# SevenSegmentBreakout.net
KiCad netlist of a schematic drawn in EAGLE
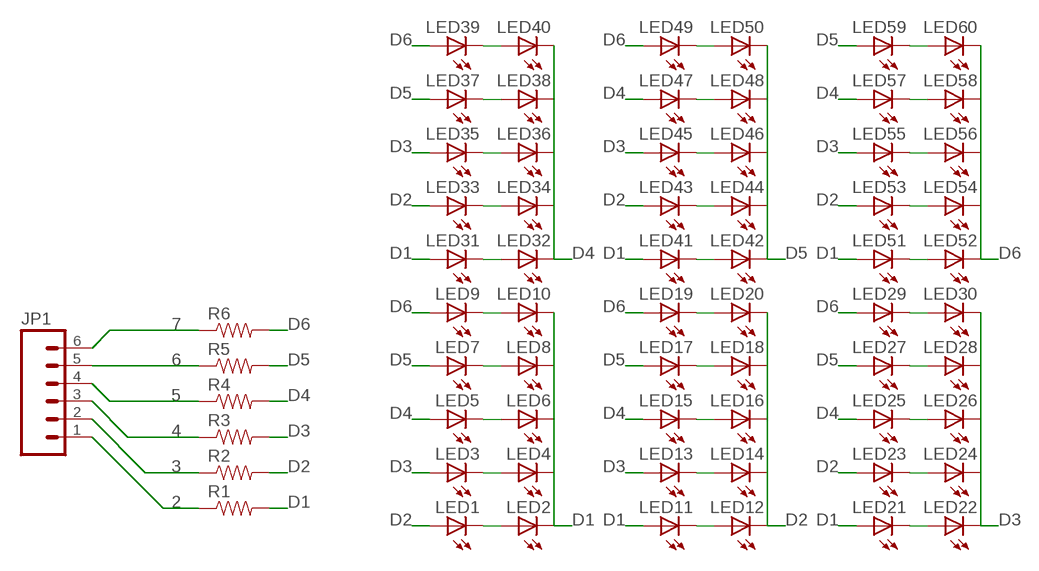
[diagram p0: schematic, sheet 1]

(export (version "E")
  (design (tool "Eeschema 10.0.6"))
  (components
    (comp (ref "JP1")
      (value "M06SIP")
      (footprint "eagle-import:1X06")
      (libsource (lib "eagle-import") (part "M06SIP"))
    )
    (comp (ref "LED1")
      (value "LEDRECT")
      (footprint "eagle-import:RECTANGLE_LED")
      (libsource (lib "eagle-import") (part "LEDRECT"))
    )
    (comp (ref "LED2")
      (value "LEDRECT")
      (footprint "eagle-import:RECTANGLE_LED")
      (libsource (lib "eagle-import") (part "LEDRECT"))
    )
    (comp (ref "LED3")
      (value "LEDRECT")
      (footprint "eagle-import:RECTANGLE_LED")
      (libsource (lib "eagle-import") (part "LEDRECT"))
    )
    (comp (ref "LED4")
      (value "LEDRECT")
      (footprint "eagle-import:RECTANGLE_LED")
      (libsource (lib "eagle-import") (part "LEDRECT"))
    )
    (comp (ref "LED5")
      (value "LEDRECT")
      (footprint "eagle-import:RECTANGLE_LED")
      (libsource (lib "eagle-import") (part "LEDRECT"))
    )
    (comp (ref "LED6")
      (value "LEDRECT")
      (footprint "eagle-import:RECTANGLE_LED")
      (libsource (lib "eagle-import") (part "LEDRECT"))
    )
    (comp (ref "LED7")
      (value "LEDRECT")
      (footprint "eagle-import:RECTANGLE_LED")
      (libsource (lib "eagle-import") (part "LEDRECT"))
    )
    (comp (ref "LED8")
      (value "LEDRECT")
      (footprint "eagle-import:RECTANGLE_LED")
      (libsource (lib "eagle-import") (part "LEDRECT"))
    )
    (comp (ref "LED9")
      (value "LEDRECT")
      (footprint "eagle-import:RECTANGLE_LED")
      (libsource (lib "eagle-import") (part "LEDRECT"))
    )
    (comp (ref "LED10")
      (value "LEDRECT")
      (footprint "eagle-import:RECTANGLE_LED")
      (libsource (lib "eagle-import") (part "LEDRECT"))
    )
    (comp (ref "LED11")
      (value "LEDRECT")
      (footprint "eagle-import:RECTANGLE_LED")
      (libsource (lib "eagle-import") (part "LEDRECT"))
    )
    (comp (ref "LED12")
      (value "LEDRECT")
      (footprint "eagle-import:RECTANGLE_LED")
      (libsource (lib "eagle-import") (part "LEDRECT"))
    )
    (comp (ref "LED13")
      (value "LEDRECT")
      (footprint "eagle-import:RECTANGLE_LED")
      (libsource (lib "eagle-import") (part "LEDRECT"))
    )
    (comp (ref "LED14")
      (value "LEDRECT")
      (footprint "eagle-import:RECTANGLE_LED")
      (libsource (lib "eagle-import") (part "LEDRECT"))
    )
    (comp (ref "LED15")
      (value "LEDRECT")
      (footprint "eagle-import:RECTANGLE_LED")
      (libsource (lib "eagle-import") (part "LEDRECT"))
    )
    (comp (ref "LED16")
      (value "LEDRECT")
      (footprint "eagle-import:RECTANGLE_LED")
      (libsource (lib "eagle-import") (part "LEDRECT"))
    )
    (comp (ref "LED17")
      (value "LEDRECT")
      (footprint "eagle-import:RECTANGLE_LED")
      (libsource (lib "eagle-import") (part "LEDRECT"))
    )
    (comp (ref "LED18")
      (value "LEDRECT")
      (footprint "eagle-import:RECTANGLE_LED")
      (libsource (lib "eagle-import") (part "LEDRECT"))
    )
    (comp (ref "LED19")
      (value "LEDRECT")
      (footprint "eagle-import:RECTANGLE_LED")
      (libsource (lib "eagle-import") (part "LEDRECT"))
    )
    (comp (ref "LED20")
      (value "LEDRECT")
      (footprint "eagle-import:RECTANGLE_LED")
      (libsource (lib "eagle-import") (part "LEDRECT"))
    )
    (comp (ref "LED21")
      (value "LEDRECT")
      (footprint "eagle-import:RECTANGLE_LED")
      (libsource (lib "eagle-import") (part "LEDRECT"))
    )
    (comp (ref "LED22")
      (value "LEDRECT")
      (footprint "eagle-import:RECTANGLE_LED")
      (libsource (lib "eagle-import") (part "LEDRECT"))
    )
    (comp (ref "LED23")
      (value "LEDRECT")
      (footprint "eagle-import:RECTANGLE_LED")
      (libsource (lib "eagle-import") (part "LEDRECT"))
    )
    (comp (ref "LED24")
      (value "LEDRECT")
      (footprint "eagle-import:RECTANGLE_LED")
      (libsource (lib "eagle-import") (part "LEDRECT"))
    )
    (comp (ref "LED25")
      (value "LEDRECT")
      (footprint "eagle-import:RECTANGLE_LED")
      (libsource (lib "eagle-import") (part "LEDRECT"))
    )
    (comp (ref "LED26")
      (value "LEDRECT")
      (footprint "eagle-import:RECTANGLE_LED")
      (libsource (lib "eagle-import") (part "LEDRECT"))
    )
    (comp (ref "LED27")
      (value "LEDRECT")
      (footprint "eagle-import:RECTANGLE_LED")
      (libsource (lib "eagle-import") (part "LEDRECT"))
    )
    (comp (ref "LED28")
      (value "LEDRECT")
      (footprint "eagle-import:RECTANGLE_LED")
      (libsource (lib "eagle-import") (part "LEDRECT"))
    )
    (comp (ref "LED29")
      (value "LEDRECT")
      (footprint "eagle-import:RECTANGLE_LED")
      (libsource (lib "eagle-import") (part "LEDRECT"))
    )
    (comp (ref "LED30")
      (value "LEDRECT")
      (footprint "eagle-import:RECTANGLE_LED")
      (libsource (lib "eagle-import") (part "LEDRECT"))
    )
    (comp (ref "LED31")
      (value "LEDRECT")
      (footprint "eagle-import:RECTANGLE_LED")
      (libsource (lib "eagle-import") (part "LEDRECT"))
    )
    (comp (ref "LED32")
      (value "LEDRECT")
      (footprint "eagle-import:RECTANGLE_LED")
      (libsource (lib "eagle-import") (part "LEDRECT"))
    )
    (comp (ref "LED33")
      (value "LEDRECT")
      (footprint "eagle-import:RECTANGLE_LED")
      (libsource (lib "eagle-import") (part "LEDRECT"))
    )
    (comp (ref "LED34")
      (value "LEDRECT")
      (footprint "eagle-import:RECTANGLE_LED")
      (libsource (lib "eagle-import") (part "LEDRECT"))
    )
    (comp (ref "LED35")
      (value "LEDRECT")
      (footprint "eagle-import:RECTANGLE_LED")
      (libsource (lib "eagle-import") (part "LEDRECT"))
    )
    (comp (ref "LED36")
      (value "LEDRECT")
      (footprint "eagle-import:RECTANGLE_LED")
      (libsource (lib "eagle-import") (part "LEDRECT"))
    )
    (comp (ref "LED37")
      (value "LEDRECT")
      (footprint "eagle-import:RECTANGLE_LED")
      (libsource (lib "eagle-import") (part "LEDRECT"))
    )
    (comp (ref "LED38")
      (value "LEDRECT")
      (footprint "eagle-import:RECTANGLE_LED")
      (libsource (lib "eagle-import") (part "LEDRECT"))
    )
    (comp (ref "LED39")
      (value "LEDRECT")
      (footprint "eagle-import:RECTANGLE_LED")
      (libsource (lib "eagle-import") (part "LEDRECT"))
    )
    (comp (ref "LED40")
      (value "LEDRECT")
      (footprint "eagle-import:RECTANGLE_LED")
      (libsource (lib "eagle-import") (part "LEDRECT"))
    )
    (comp (ref "LED41")
      (value "LEDRECT")
      (footprint "eagle-import:RECTANGLE_LED")
      (libsource (lib "eagle-import") (part "LEDRECT"))
    )
    (comp (ref "LED42")
      (value "LEDRECT")
      (footprint "eagle-import:RECTANGLE_LED")
      (libsource (lib "eagle-import") (part "LEDRECT"))
    )
    (comp (ref "LED43")
      (value "LEDRECT")
      (footprint "eagle-import:RECTANGLE_LED")
      (libsource (lib "eagle-import") (part "LEDRECT"))
    )
    (comp (ref "LED44")
      (value "LEDRECT")
      (footprint "eagle-import:RECTANGLE_LED")
      (libsource (lib "eagle-import") (part "LEDRECT"))
    )
    (comp (ref "LED45")
      (value "LEDRECT")
      (footprint "eagle-import:RECTANGLE_LED")
      (libsource (lib "eagle-import") (part "LEDRECT"))
    )
    (comp (ref "LED46")
      (value "LEDRECT")
      (footprint "eagle-import:RECTANGLE_LED")
      (libsource (lib "eagle-import") (part "LEDRECT"))
    )
    (comp (ref "LED47")
      (value "LEDRECT")
      (footprint "eagle-import:RECTANGLE_LED")
      (libsource (lib "eagle-import") (part "LEDRECT"))
    )
    (comp (ref "LED48")
      (value "LEDRECT")
      (footprint "eagle-import:RECTANGLE_LED")
      (libsource (lib "eagle-import") (part "LEDRECT"))
    )
    (comp (ref "LED49")
      (value "LEDRECT")
      (footprint "eagle-import:RECTANGLE_LED")
      (libsource (lib "eagle-import") (part "LEDRECT"))
    )
    (comp (ref "LED50")
      (value "LEDRECT")
      (footprint "eagle-import:RECTANGLE_LED")
      (libsource (lib "eagle-import") (part "LEDRECT"))
    )
    (comp (ref "LED51")
      (value "LEDRECT")
      (footprint "eagle-import:RECTANGLE_LED")
      (libsource (lib "eagle-import") (part "LEDRECT"))
    )
    (comp (ref "LED52")
      (value "LEDRECT")
      (footprint "eagle-import:RECTANGLE_LED")
      (libsource (lib "eagle-import") (part "LEDRECT"))
    )
    (comp (ref "LED53")
      (value "LEDRECT")
      (footprint "eagle-import:RECTANGLE_LED")
      (libsource (lib "eagle-import") (part "LEDRECT"))
    )
    (comp (ref "LED54")
      (value "LEDRECT")
      (footprint "eagle-import:RECTANGLE_LED")
      (libsource (lib "eagle-import") (part "LEDRECT"))
    )
    (comp (ref "LED55")
      (value "LEDRECT")
      (footprint "eagle-import:RECTANGLE_LED")
      (libsource (lib "eagle-import") (part "LEDRECT"))
    )
    (comp (ref "LED56")
      (value "LEDRECT")
      (footprint "eagle-import:RECTANGLE_LED")
      (libsource (lib "eagle-import") (part "LEDRECT"))
    )
    (comp (ref "LED57")
      (value "LEDOVAL")
      (footprint "eagle-import:LED-OVAL")
      (libsource (lib "eagle-import") (part "LEDOVAL"))
    )
    (comp (ref "LED58")
      (value "LEDOVAL")
      (footprint "eagle-import:LED-OVAL")
      (libsource (lib "eagle-import") (part "LEDOVAL"))
    )
    (comp (ref "LED59")
      (value "LEDOVAL")
      (footprint "eagle-import:LED-OVAL")
      (libsource (lib "eagle-import") (part "LEDOVAL"))
    )
    (comp (ref "LED60")
      (value "LEDOVAL")
      (footprint "eagle-import:LED-OVAL")
      (libsource (lib "eagle-import") (part "LEDOVAL"))
    )
    (comp (ref "R1")
      (value "RESISTORAXIAL-0.3")
      (footprint "eagle-import:AXIAL-0.3")
      (libsource (lib "eagle-import") (part "RESISTORAXIAL-0.3"))
    )
    (comp (ref "R2")
      (value "RESISTORAXIAL-0.3")
      (footprint "eagle-import:AXIAL-0.3")
      (libsource (lib "eagle-import") (part "RESISTORAXIAL-0.3"))
    )
    (comp (ref "R3")
      (value "RESISTORAXIAL-0.3")
      (footprint "eagle-import:AXIAL-0.3")
      (libsource (lib "eagle-import") (part "RESISTORAXIAL-0.3"))
    )
    (comp (ref "R4")
      (value "RESISTORAXIAL-0.3")
      (footprint "eagle-import:AXIAL-0.3")
      (libsource (lib "eagle-import") (part "RESISTORAXIAL-0.3"))
    )
    (comp (ref "R5")
      (value "RESISTORAXIAL-0.3")
      (footprint "eagle-import:AXIAL-0.3")
      (libsource (lib "eagle-import") (part "RESISTORAXIAL-0.3"))
    )
    (comp (ref "R6")
      (value "RESISTORAXIAL-0.3")
      (footprint "eagle-import:AXIAL-0.3")
      (libsource (lib "eagle-import") (part "RESISTORAXIAL-0.3"))
    )
  )
  (nets
    (net (code "1") (name "/2") (class "Default")
      (node (ref "JP1") (pin "1") (pinfunction "1_1") (pintype "passive"))
      (node (ref "R1") (pin "P$1") (pinfunction "1_P$1") (pintype "passive"))
    )
    (net (code "2") (name "/3") (class "Default")
      (node (ref "JP1") (pin "2") (pinfunction "2_2") (pintype "passive"))
      (node (ref "R2") (pin "P$1") (pinfunction "1_P$1") (pintype "passive"))
    )
    (net (code "3") (name "/4") (class "Default")
      (node (ref "JP1") (pin "3") (pinfunction "3_3") (pintype "passive"))
      (node (ref "R3") (pin "P$1") (pinfunction "1_P$1") (pintype "passive"))
    )
    (net (code "4") (name "/5") (class "Default")
      (node (ref "JP1") (pin "4") (pinfunction "4_4") (pintype "passive"))
      (node (ref "R4") (pin "P$1") (pinfunction "1_P$1") (pintype "passive"))
    )
    (net (code "5") (name "/6") (class "Default")
      (node (ref "JP1") (pin "5") (pinfunction "5_5") (pintype "passive"))
      (node (ref "R5") (pin "P$1") (pinfunction "1_P$1") (pintype "passive"))
    )
    (net (code "6") (name "/7") (class "Default")
      (node (ref "JP1") (pin "6") (pinfunction "6_6") (pintype "passive"))
      (node (ref "R6") (pin "P$1") (pinfunction "1_P$1") (pintype "passive"))
    )
    (net (code "7") (name "/D1") (class "Default")
      (node (ref "LED10") (pin "C") (pinfunction "C_C") (pintype "passive"))
      (node (ref "LED11") (pin "A") (pinfunction "A_A") (pintype "passive"))
      (node (ref "LED2") (pin "C") (pinfunction "C_C") (pintype "passive"))
      (node (ref "LED21") (pin "A") (pinfunction "A_A") (pintype "passive"))
      (node (ref "LED31") (pin "A") (pinfunction "A_A") (pintype "passive"))
      (node (ref "LED4") (pin "C") (pinfunction "C_C") (pintype "passive"))
      (node (ref "LED41") (pin "A") (pinfunction "A_A") (pintype "passive"))
      (node (ref "LED51") (pin "A") (pinfunction "A_A") (pintype "passive"))
      (node (ref "LED6") (pin "C") (pinfunction "C_C") (pintype "passive"))
      (node (ref "LED8") (pin "C") (pinfunction "C_C") (pintype "passive"))
      (node (ref "R1") (pin "P$2") (pinfunction "2_P$2") (pintype "passive"))
    )
    (net (code "8") (name "/D2") (class "Default")
      (node (ref "LED1") (pin "A") (pinfunction "A_A") (pintype "passive"))
      (node (ref "LED12") (pin "C") (pinfunction "C_C") (pintype "passive"))
      (node (ref "LED14") (pin "C") (pinfunction "C_C") (pintype "passive"))
      (node (ref "LED16") (pin "C") (pinfunction "C_C") (pintype "passive"))
      (node (ref "LED18") (pin "C") (pinfunction "C_C") (pintype "passive"))
      (node (ref "LED20") (pin "C") (pinfunction "C_C") (pintype "passive"))
      (node (ref "LED23") (pin "A") (pinfunction "A_A") (pintype "passive"))
      (node (ref "LED33") (pin "A") (pinfunction "A_A") (pintype "passive"))
      (node (ref "LED43") (pin "A") (pinfunction "A_A") (pintype "passive"))
      (node (ref "LED53") (pin "A") (pinfunction "A_A") (pintype "passive"))
      (node (ref "R2") (pin "P$2") (pinfunction "2_P$2") (pintype "passive"))
    )
    (net (code "9") (name "/D3") (class "Default")
      (node (ref "LED13") (pin "A") (pinfunction "A_A") (pintype "passive"))
      (node (ref "LED22") (pin "C") (pinfunction "C_C") (pintype "passive"))
      (node (ref "LED24") (pin "C") (pinfunction "C_C") (pintype "passive"))
      (node (ref "LED26") (pin "C") (pinfunction "C_C") (pintype "passive"))
      (node (ref "LED28") (pin "C") (pinfunction "C_C") (pintype "passive"))
      (node (ref "LED3") (pin "A") (pinfunction "A_A") (pintype "passive"))
      (node (ref "LED30") (pin "C") (pinfunction "C_C") (pintype "passive"))
      (node (ref "LED35") (pin "A") (pinfunction "A_A") (pintype "passive"))
      (node (ref "LED45") (pin "A") (pinfunction "A_A") (pintype "passive"))
      (node (ref "LED55") (pin "A") (pinfunction "A_A") (pintype "passive"))
      (node (ref "R3") (pin "P$2") (pinfunction "2_P$2") (pintype "passive"))
    )
    (net (code "10") (name "/D4") (class "Default")
      (node (ref "LED15") (pin "A") (pinfunction "A_A") (pintype "passive"))
      (node (ref "LED25") (pin "A") (pinfunction "A_A") (pintype "passive"))
      (node (ref "LED32") (pin "C") (pinfunction "C_C") (pintype "passive"))
      (node (ref "LED34") (pin "C") (pinfunction "C_C") (pintype "passive"))
      (node (ref "LED36") (pin "C") (pinfunction "C_C") (pintype "passive"))
      (node (ref "LED38") (pin "C") (pinfunction "C_C") (pintype "passive"))
      (node (ref "LED40") (pin "C") (pinfunction "C_C") (pintype "passive"))
      (node (ref "LED47") (pin "A") (pinfunction "A_A") (pintype "passive"))
      (node (ref "LED5") (pin "A") (pinfunction "A_A") (pintype "passive"))
      (node (ref "LED57") (pin "ANODE") (pinfunction "A_ANODE") (pintype "passive"))
      (node (ref "R4") (pin "P$2") (pinfunction "2_P$2") (pintype "passive"))
    )
    (net (code "11") (name "/D5") (class "Default")
      (node (ref "LED17") (pin "A") (pinfunction "A_A") (pintype "passive"))
      (node (ref "LED27") (pin "A") (pinfunction "A_A") (pintype "passive"))
      (node (ref "LED37") (pin "A") (pinfunction "A_A") (pintype "passive"))
      (node (ref "LED42") (pin "C") (pinfunction "C_C") (pintype "passive"))
      (node (ref "LED44") (pin "C") (pinfunction "C_C") (pintype "passive"))
      (node (ref "LED46") (pin "C") (pinfunction "C_C") (pintype "passive"))
      (node (ref "LED48") (pin "C") (pinfunction "C_C") (pintype "passive"))
      (node (ref "LED50") (pin "C") (pinfunction "C_C") (pintype "passive"))
      (node (ref "LED59") (pin "ANODE") (pinfunction "A_ANODE") (pintype "passive"))
      (node (ref "LED7") (pin "A") (pinfunction "A_A") (pintype "passive"))
      (node (ref "R5") (pin "P$2") (pinfunction "2_P$2") (pintype "passive"))
    )
    (net (code "12") (name "/D6") (class "Default")
      (node (ref "LED19") (pin "A") (pinfunction "A_A") (pintype "passive"))
      (node (ref "LED29") (pin "A") (pinfunction "A_A") (pintype "passive"))
      (node (ref "LED39") (pin "A") (pinfunction "A_A") (pintype "passive"))
      (node (ref "LED49") (pin "A") (pinfunction "A_A") (pintype "passive"))
      (node (ref "LED52") (pin "C") (pinfunction "C_C") (pintype "passive"))
      (node (ref "LED54") (pin "C") (pinfunction "C_C") (pintype "passive"))
      (node (ref "LED56") (pin "C") (pinfunction "C_C") (pintype "passive"))
      (node (ref "LED58") (pin "CATHODE") (pinfunction "C_CATHODE") (pintype "passive"))
      (node (ref "LED60") (pin "CATHODE") (pinfunction "C_CATHODE") (pintype "passive"))
      (node (ref "LED9") (pin "A") (pinfunction "A_A") (pintype "passive"))
      (node (ref "R6") (pin "P$2") (pinfunction "2_P$2") (pintype "passive"))
    )
    (net (code "13") (name "Net-(LED1-PadC)") (class "Default")
      (node (ref "LED1") (pin "C") (pinfunction "C_C") (pintype "passive"))
      (node (ref "LED2") (pin "A") (pinfunction "A_A") (pintype "passive"))
    )
    (net (code "14") (name "Net-(LED3-PadC)") (class "Default")
      (node (ref "LED3") (pin "C") (pinfunction "C_C") (pintype "passive"))
      (node (ref "LED4") (pin "A") (pinfunction "A_A") (pintype "passive"))
    )
    (net (code "15") (name "Net-(LED5-PadC)") (class "Default")
      (node (ref "LED5") (pin "C") (pinfunction "C_C") (pintype "passive"))
      (node (ref "LED6") (pin "A") (pinfunction "A_A") (pintype "passive"))
    )
    (net (code "16") (name "Net-(LED7-PadC)") (class "Default")
      (node (ref "LED7") (pin "C") (pinfunction "C_C") (pintype "passive"))
      (node (ref "LED8") (pin "A") (pinfunction "A_A") (pintype "passive"))
    )
    (net (code "17") (name "Net-(LED10-PadA)") (class "Default")
      (node (ref "LED10") (pin "A") (pinfunction "A_A") (pintype "passive"))
      (node (ref "LED9") (pin "C") (pinfunction "C_C") (pintype "passive"))
    )
    (net (code "18") (name "Net-(LED11-PadC)") (class "Default")
      (node (ref "LED11") (pin "C") (pinfunction "C_C") (pintype "passive"))
      (node (ref "LED12") (pin "A") (pinfunction "A_A") (pintype "passive"))
    )
    (net (code "19") (name "Net-(LED13-PadC)") (class "Default")
      (node (ref "LED13") (pin "C") (pinfunction "C_C") (pintype "passive"))
      (node (ref "LED14") (pin "A") (pinfunction "A_A") (pintype "passive"))
    )
    (net (code "20") (name "Net-(LED15-PadC)") (class "Default")
      (node (ref "LED15") (pin "C") (pinfunction "C_C") (pintype "passive"))
      (node (ref "LED16") (pin "A") (pinfunction "A_A") (pintype "passive"))
    )
    (net (code "21") (name "Net-(LED17-PadC)") (class "Default")
      (node (ref "LED17") (pin "C") (pinfunction "C_C") (pintype "passive"))
      (node (ref "LED18") (pin "A") (pinfunction "A_A") (pintype "passive"))
    )
    (net (code "22") (name "Net-(LED19-PadC)") (class "Default")
      (node (ref "LED19") (pin "C") (pinfunction "C_C") (pintype "passive"))
      (node (ref "LED20") (pin "A") (pinfunction "A_A") (pintype "passive"))
    )
    (net (code "23") (name "Net-(LED21-PadC)") (class "Default")
      (node (ref "LED21") (pin "C") (pinfunction "C_C") (pintype "passive"))
      (node (ref "LED22") (pin "A") (pinfunction "A_A") (pintype "passive"))
    )
    (net (code "24") (name "Net-(LED23-PadC)") (class "Default")
      (node (ref "LED23") (pin "C") (pinfunction "C_C") (pintype "passive"))
      (node (ref "LED24") (pin "A") (pinfunction "A_A") (pintype "passive"))
    )
    (net (code "25") (name "Net-(LED25-PadC)") (class "Default")
      (node (ref "LED25") (pin "C") (pinfunction "C_C") (pintype "passive"))
      (node (ref "LED26") (pin "A") (pinfunction "A_A") (pintype "passive"))
    )
    (net (code "26") (name "Net-(LED27-PadC)") (class "Default")
      (node (ref "LED27") (pin "C") (pinfunction "C_C") (pintype "passive"))
      (node (ref "LED28") (pin "A") (pinfunction "A_A") (pintype "passive"))
    )
    (net (code "27") (name "Net-(LED29-PadC)") (class "Default")
      (node (ref "LED29") (pin "C") (pinfunction "C_C") (pintype "passive"))
      (node (ref "LED30") (pin "A") (pinfunction "A_A") (pintype "passive"))
    )
    (net (code "28") (name "Net-(LED31-PadC)") (class "Default")
      (node (ref "LED31") (pin "C") (pinfunction "C_C") (pintype "passive"))
      (node (ref "LED32") (pin "A") (pinfunction "A_A") (pintype "passive"))
    )
    (net (code "29") (name "Net-(LED33-PadC)") (class "Default")
      (node (ref "LED33") (pin "C") (pinfunction "C_C") (pintype "passive"))
      (node (ref "LED34") (pin "A") (pinfunction "A_A") (pintype "passive"))
    )
    (net (code "30") (name "Net-(LED35-PadC)") (class "Default")
      (node (ref "LED35") (pin "C") (pinfunction "C_C") (pintype "passive"))
      (node (ref "LED36") (pin "A") (pinfunction "A_A") (pintype "passive"))
    )
    (net (code "31") (name "Net-(LED37-PadC)") (class "Default")
      (node (ref "LED37") (pin "C") (pinfunction "C_C") (pintype "passive"))
      (node (ref "LED38") (pin "A") (pinfunction "A_A") (pintype "passive"))
    )
    (net (code "32") (name "Net-(LED39-PadC)") (class "Default")
      (node (ref "LED39") (pin "C") (pinfunction "C_C") (pintype "passive"))
      (node (ref "LED40") (pin "A") (pinfunction "A_A") (pintype "passive"))
    )
    (net (code "33") (name "Net-(LED41-PadC)") (class "Default")
      (node (ref "LED41") (pin "C") (pinfunction "C_C") (pintype "passive"))
      (node (ref "LED42") (pin "A") (pinfunction "A_A") (pintype "passive"))
    )
    (net (code "34") (name "Net-(LED43-PadC)") (class "Default")
      (node (ref "LED43") (pin "C") (pinfunction "C_C") (pintype "passive"))
      (node (ref "LED44") (pin "A") (pinfunction "A_A") (pintype "passive"))
    )
    (net (code "35") (name "Net-(LED45-PadC)") (class "Default")
      (node (ref "LED45") (pin "C") (pinfunction "C_C") (pintype "passive"))
      (node (ref "LED46") (pin "A") (pinfunction "A_A") (pintype "passive"))
    )
    (net (code "36") (name "Net-(LED47-PadC)") (class "Default")
      (node (ref "LED47") (pin "C") (pinfunction "C_C") (pintype "passive"))
      (node (ref "LED48") (pin "A") (pinfunction "A_A") (pintype "passive"))
    )
    (net (code "37") (name "Net-(LED49-PadC)") (class "Default")
      (node (ref "LED49") (pin "C") (pinfunction "C_C") (pintype "passive"))
      (node (ref "LED50") (pin "A") (pinfunction "A_A") (pintype "passive"))
    )
    (net (code "38") (name "Net-(LED51-PadC)") (class "Default")
      (node (ref "LED51") (pin "C") (pinfunction "C_C") (pintype "passive"))
      (node (ref "LED52") (pin "A") (pinfunction "A_A") (pintype "passive"))
    )
    (net (code "39") (name "Net-(LED53-PadC)") (class "Default")
      (node (ref "LED53") (pin "C") (pinfunction "C_C") (pintype "passive"))
      (node (ref "LED54") (pin "A") (pinfunction "A_A") (pintype "passive"))
    )
    (net (code "40") (name "Net-(LED55-PadC)") (class "Default")
      (node (ref "LED55") (pin "C") (pinfunction "C_C") (pintype "passive"))
      (node (ref "LED56") (pin "A") (pinfunction "A_A") (pintype "passive"))
    )
    (net (code "41") (name "Net-(LED57-C)") (class "Default")
      (node (ref "LED57") (pin "CATHODE") (pinfunction "C_CATHODE") (pintype "passive"))
      (node (ref "LED58") (pin "ANODE") (pinfunction "A_ANODE") (pintype "passive"))
    )
    (net (code "42") (name "Net-(LED59-C)") (class "Default")
      (node (ref "LED59") (pin "CATHODE") (pinfunction "C_CATHODE") (pintype "passive"))
      (node (ref "LED60") (pin "ANODE") (pinfunction "A_ANODE") (pintype "passive"))
    )
  )
)
